# radar.net
KiCad netlist of a schematic drawn in EAGLE
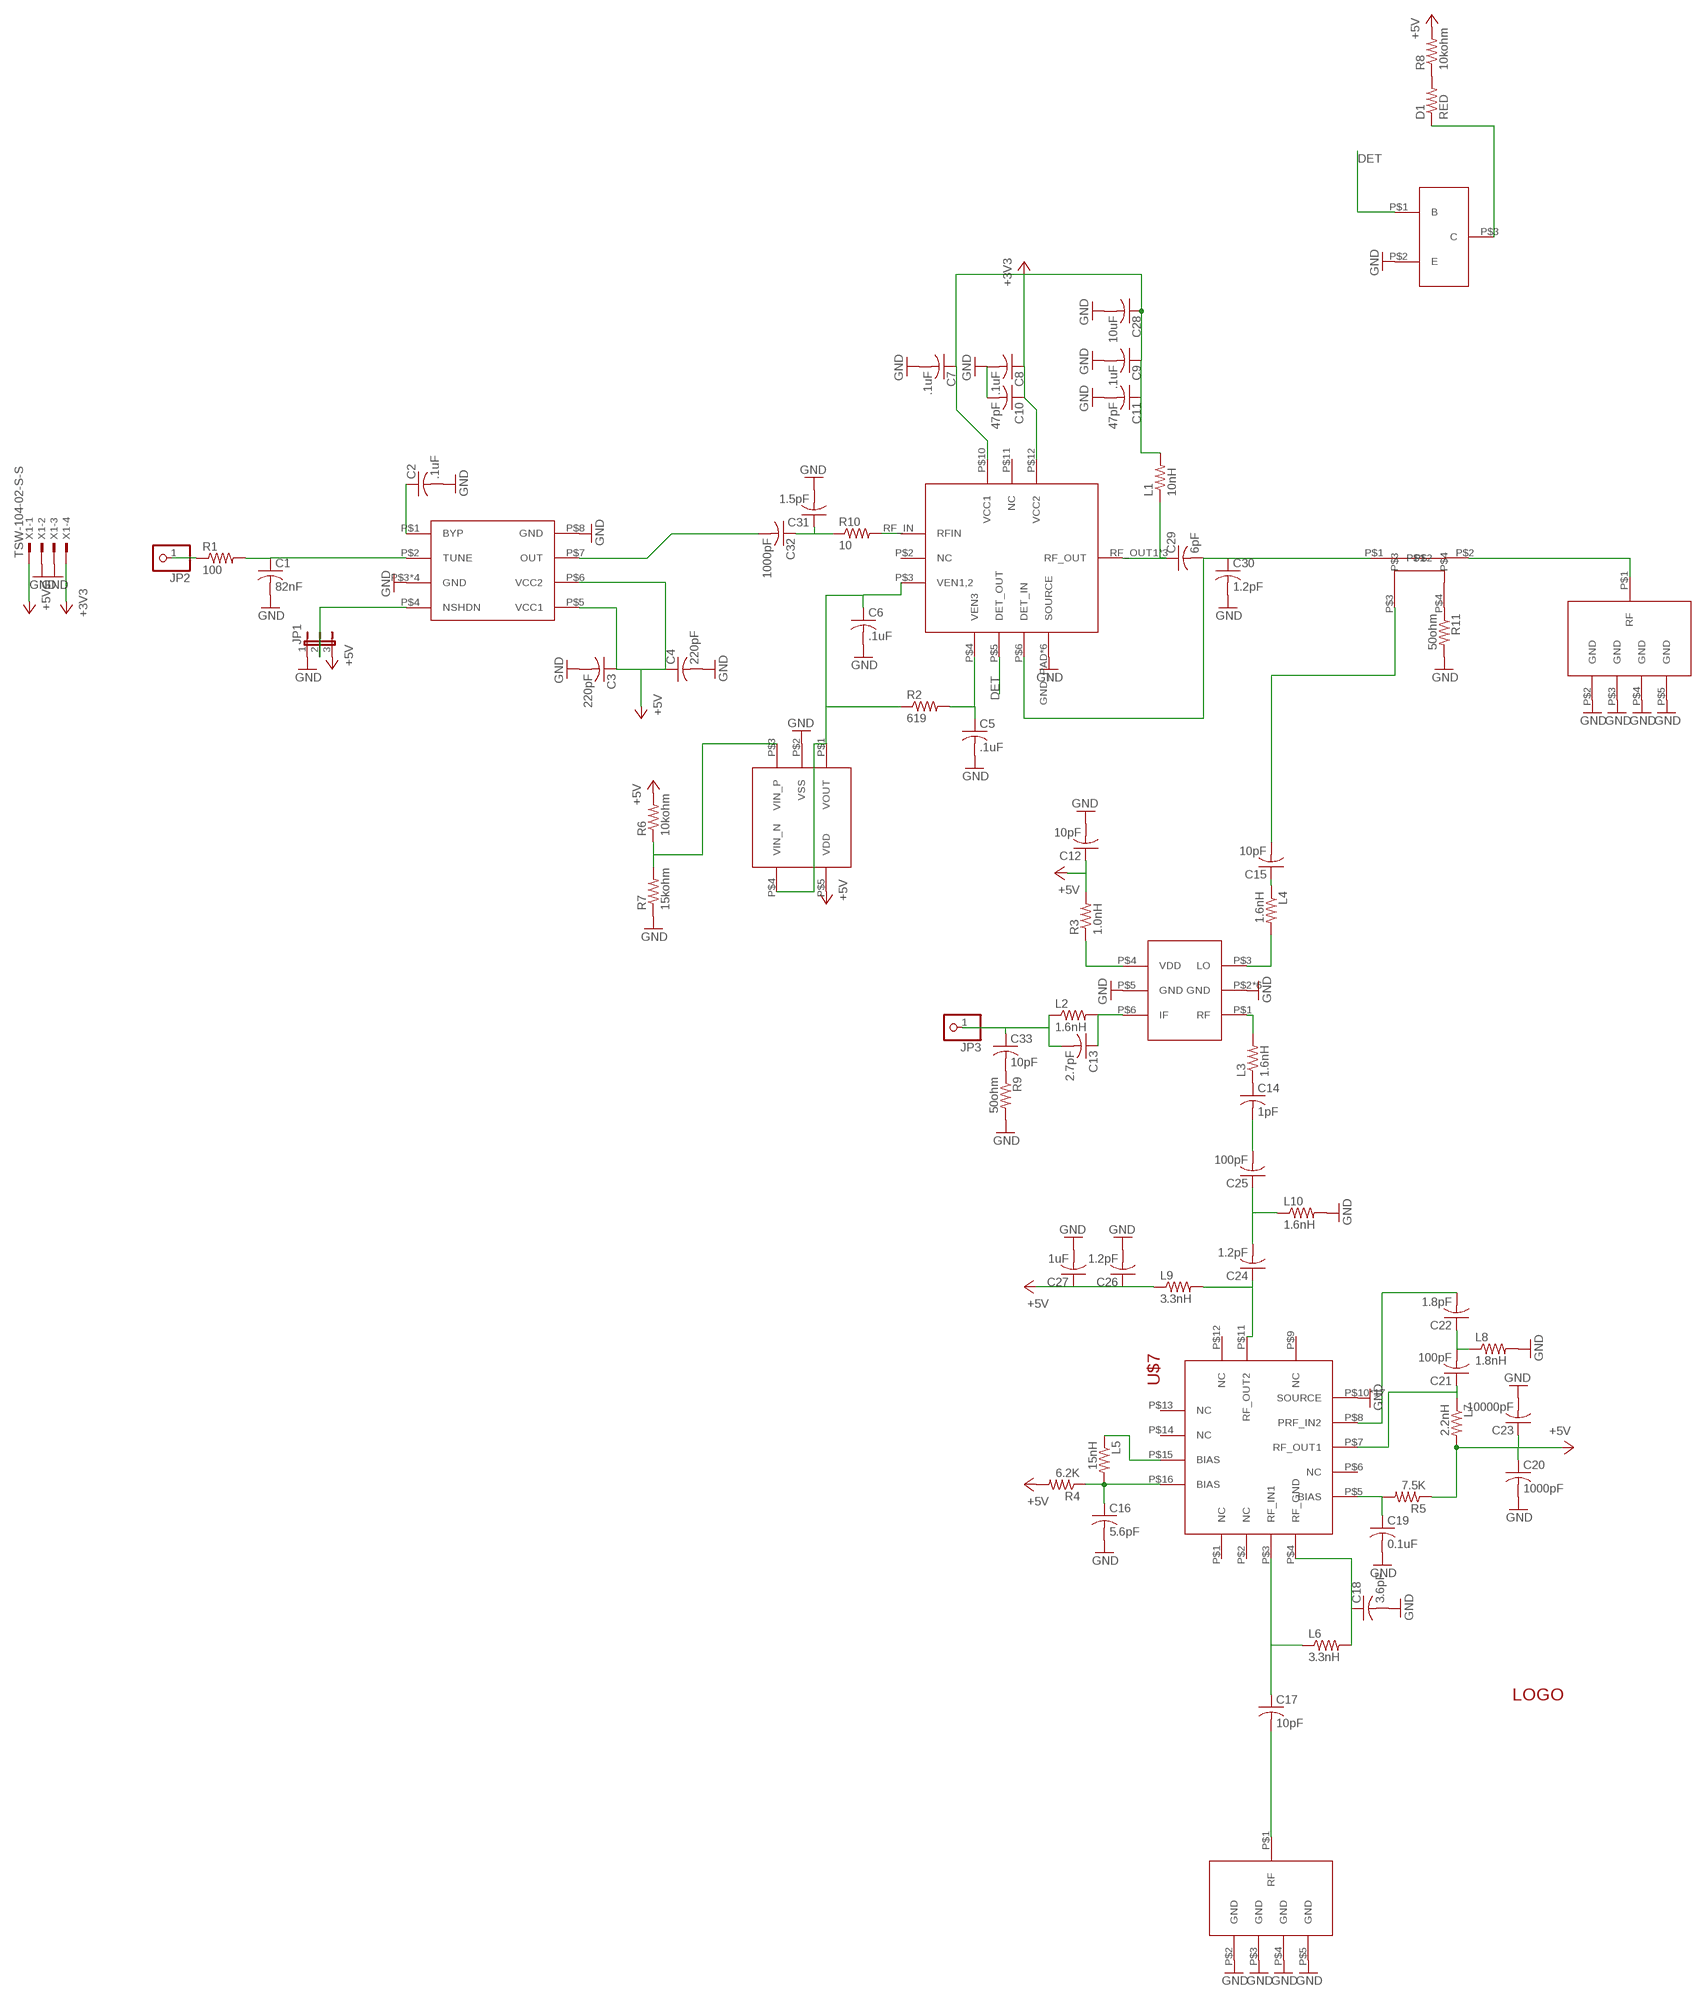
[diagram p0: schematic, sheet 1]

(export (version "E")
  (design (tool "Eeschema 10.0.6"))
  (components
    (comp (ref "C1")
      (value "82nF")
      (footprint "eagle-import:C3216")
      (fields (field (name "MANUFACTURER") "Vishay") (field (name "PART#") "VJ1206Y823MXBTW1BC"))
      (libsource (lib "eagle-import") (part "resistor_C-USC3216"))
    )
    (comp (ref "C2")
      (value ".1uF")
      (footprint "eagle-import:C0805")
      (fields (field (name "MANUFACTURER") "Vishay") (field (name "PART#") "VJ0805Y104MXXAC"))
      (libsource (lib "eagle-import") (part "C-USC0805"))
    )
    (comp (ref "C3")
      (value "220pF")
      (footprint "eagle-import:C0805")
      (fields (field (name "MANUFACTURER") "Vishay") (field (name "PART#") "VJ0805A221JXAPW1BC"))
      (libsource (lib "eagle-import") (part "C-USC0805"))
    )
    (comp (ref "C4")
      (value "220pF")
      (footprint "eagle-import:C0805")
      (fields (field (name "MANUFACTURER") "Vishay") (field (name "PART#") "VJ0805A221JXAPW1BC"))
      (libsource (lib "eagle-import") (part "C-USC0805"))
    )
    (comp (ref "C5")
      (value ".1uF")
      (footprint "eagle-import:C0805")
      (fields (field (name "MANUFACTURER") "Vishay") (field (name "PART#") "VJ0805Y104MXXAC"))
      (libsource (lib "eagle-import") (part "C-USC0805"))
    )
    (comp (ref "C6")
      (value ".1uF")
      (footprint "eagle-import:C0805")
      (fields (field (name "MANUFACTURER") "Vishay") (field (name "PART#") "VJ0805Y104MXXAC"))
      (libsource (lib "eagle-import") (part "C-USC0805"))
    )
    (comp (ref "C7")
      (value ".1uF")
      (footprint "eagle-import:C0805")
      (fields (field (name "MANUFACTURER") "Vishay") (field (name "PART#") "VJ0805Y104MXXAC"))
      (libsource (lib "eagle-import") (part "C-USC0805"))
    )
    (comp (ref "C8")
      (value ".1uF")
      (footprint "eagle-import:C0805")
      (fields (field (name "MANUFACTURER") "Vishay") (field (name "PART#") "VJ0805Y104MXXAC"))
      (libsource (lib "eagle-import") (part "C-USC0805"))
    )
    (comp (ref "C9")
      (value ".1uF")
      (footprint "eagle-import:C0805")
      (fields (field (name "MANUFACTURER") "Vishay") (field (name "PART#") "VJ0805Y104MXXAC"))
      (libsource (lib "eagle-import") (part "C-USC0805"))
    )
    (comp (ref "C10")
      (value "47pF")
      (footprint "eagle-import:C0805")
      (fields (field (name "MANUFACTURER") "Vishay") (field (name "PART#") "VJ0805A470GXACW1BC"))
      (libsource (lib "eagle-import") (part "C-USC0805"))
    )
    (comp (ref "C11")
      (value "47pF")
      (footprint "eagle-import:C0805")
      (fields (field (name "MANUFACTURER") "Vishay") (field (name "PART#") "VJ0805A470GXACW1BC"))
      (libsource (lib "eagle-import") (part "C-USC0805"))
    )
    (comp (ref "C12")
      (value "10pF")
      (footprint "eagle-import:C0805")
      (fields (field (name "MANUFACTURER") "Vishay") (field (name "PART#") "VJ0603A100JXACW1BC"))
      (libsource (lib "eagle-import") (part "C-USC0805"))
    )
    (comp (ref "C13")
      (value "2.7pF")
      (footprint "eagle-import:C0603")
      (fields (field (name "MANUFACTURER") "Vishay") (field (name "PART#") "VJ0603A2R7CXACW1BC"))
      (libsource (lib "eagle-import") (part "C-USC0603"))
    )
    (comp (ref "C14")
      (value "1pF")
      (footprint "eagle-import:C0603")
      (fields (field (name "MANUFACTURER") "Vishay") (field (name "PART#") "VJ0603A1R0CXACW1BC"))
      (libsource (lib "eagle-import") (part "C-USC0603"))
    )
    (comp (ref "C15")
      (value "10pF")
      (footprint "eagle-import:C0603")
      (fields (field (name "MANUFACTURER") "Vishay") (field (name "PART#") "VJ0603A2R7CXACW1BC"))
      (libsource (lib "eagle-import") (part "C-USC0603"))
    )
    (comp (ref "C16")
      (value "5.6pF")
      (footprint "eagle-import:C0603")
      (fields (field (name "MANUFACTURER") "Vishay") (field (name "PART#") "VJ0603A5R6CXACW1BC"))
      (libsource (lib "eagle-import") (part "C-USC0603"))
    )
    (comp (ref "C17")
      (value "10pF")
      (footprint "eagle-import:C0603")
      (fields (field (name "MANUFACTURER") "Vishay") (field (name "PART#") "VJ0603A100JXACW1BC"))
      (libsource (lib "eagle-import") (part "C-USC0603"))
    )
    (comp (ref "C18")
      (value "3.6pF")
      (footprint "eagle-import:C0603")
      (fields (field (name "MANUFACTURER") "Vishay") (field (name "PART#") "VJ0603A3R9CXACW1BC"))
      (libsource (lib "eagle-import") (part "C-USC0603"))
    )
    (comp (ref "C19")
      (value "0.1uF")
      (footprint "eagle-import:C0603")
      (fields (field (name "MANUFACTURER") "Vishay") (field (name "PART#") "VJ0603A3R9CXACW1BC"))
      (libsource (lib "eagle-import") (part "C-USC0603"))
    )
    (comp (ref "C20")
      (value "1000pF")
      (footprint "eagle-import:C0603")
      (fields (field (name "MANUFACTURER") "Vishay") (field (name "PART#") "VJ0603A3R9CXACW1BC"))
      (libsource (lib "eagle-import") (part "C-USC0603"))
    )
    (comp (ref "C21")
      (value "100pF")
      (footprint "eagle-import:C0603")
      (fields (field (name "MANUFACTURER") "Vishay") (field (name "PART#") "VJ0603A3R9CXACW1BC"))
      (libsource (lib "eagle-import") (part "C-USC0603"))
    )
    (comp (ref "C22")
      (value "1.8pF")
      (footprint "eagle-import:C0603")
      (fields (field (name "MANUFACTURER") "Vishay") (field (name "PART#") "VJ0603A3R9CXACW1BC"))
      (libsource (lib "eagle-import") (part "C-USC0603"))
    )
    (comp (ref "C23")
      (value "10000pF")
      (footprint "eagle-import:C0603")
      (fields (field (name "MANUFACTURER") "Vishay") (field (name "PART#") "VJ0603A3R9CXACW1BC"))
      (libsource (lib "eagle-import") (part "C-USC0603"))
    )
    (comp (ref "C24")
      (value "1.2pF")
      (footprint "eagle-import:C0603")
      (fields (field (name "MANUFACTURER") "Vishay") (field (name "PART#") "VJ0603A3R9CXACW1BC"))
      (libsource (lib "eagle-import") (part "C-USC0603"))
    )
    (comp (ref "C25")
      (value "100pF")
      (footprint "eagle-import:C0603")
      (fields (field (name "MANUFACTURER") "Vishay") (field (name "PART#") "VJ0603A3R9CXACW1BC"))
      (libsource (lib "eagle-import") (part "C-USC0603"))
    )
    (comp (ref "C26")
      (value "1.2pF")
      (footprint "eagle-import:C0603")
      (fields (field (name "MANUFACTURER") "Vishay") (field (name "PART#") "VJ0603A3R9CXACW1BC"))
      (libsource (lib "eagle-import") (part "C-USC0603"))
    )
    (comp (ref "C27")
      (value "1uF")
      (footprint "eagle-import:C0603")
      (fields (field (name "MANUFACTURER") "Vishay") (field (name "PART#") "VJ0603A3R9CXACW1BC"))
      (libsource (lib "eagle-import") (part "C-USC0603"))
    )
    (comp (ref "C28")
      (value "10uF")
      (footprint "eagle-import:C1206")
      (fields (field (name "MANUFACTURER") "Vishay") (field (name "PART#") "VJ1206V106ZXQTW1BC"))
      (libsource (lib "eagle-import") (part "C-USC1206"))
    )
    (comp (ref "C29")
      (value "6pF")
      (footprint "eagle-import:C0603")
      (fields (field (name "MANUFACTURER") "Vishay") (field (name "PART#") "VJ0805Y104MXXAC"))
      (libsource (lib "eagle-import") (part "C-USC0603"))
    )
    (comp (ref "C30")
      (value "1.2pF")
      (footprint "eagle-import:C0603")
      (fields (field (name "MANUFACTURER") "Vishay") (field (name "PART#") "VJ0805Y104MXXAC"))
      (libsource (lib "eagle-import") (part "C-USC0603"))
    )
    (comp (ref "C31")
      (value "1.5pF")
      (footprint "eagle-import:C0603K")
      (fields (field (name "MANUFACTURER") "Vishay") (field (name "PART#") "VJ0805Y104MXXAC"))
      (libsource (lib "eagle-import") (part "C-USC0603K"))
    )
    (comp (ref "C32")
      (value "1000pF")
      (footprint "eagle-import:C0603K")
      (fields (field (name "MANUFACTURER") "Vishay") (field (name "PART#") "VJ0805Y104MXXAC"))
      (libsource (lib "eagle-import") (part "C-USC0603K"))
    )
    (comp (ref "C33")
      (value "10pF")
      (footprint "eagle-import:C0805")
      (fields (field (name "MANUFACTURER") "Vishay") (field (name "PART#") "VJ0805A100GXAPW1BC"))
      (libsource (lib "eagle-import") (part "C-USC0805"))
    )
    (comp (ref "D1")
      (value "RED")
      (footprint "eagle-import:R1206")
      (fields (field (name "MANUFACTURER") "Vishay") (field (name "PART#") "VJ1206Y823MXBTW1BC"))
      (libsource (lib "eagle-import") (part "R-US_R1206"))
    )
    (comp (ref "JP1")
      (value "JP2E")
      (footprint "eagle-import:JP2")
      (libsource (lib "eagle-import") (part "JP2E"))
    )
    (comp (ref "JP2")
      (value "PINHD-1X1")
      (footprint "eagle-import:1X01")
      (libsource (lib "eagle-import") (part "PINHD-1X1"))
    )
    (comp (ref "JP3")
      (value "PINHD-1X1")
      (footprint "eagle-import:1X01")
      (libsource (lib "eagle-import") (part "PINHD-1X1"))
    )
    (comp (ref "L1")
      (value "10nH")
      (footprint "eagle-import:R0603")
      (fields (field (name "MANUFACTURER") "Taiyo Yuden") (field (name "PART#") "HK060310NJ-T"))
      (libsource (lib "eagle-import") (part "R-US_R0603"))
    )
    (comp (ref "L2")
      (value "1.6nH")
      (footprint "eagle-import:R0603")
      (fields (field (name "MANUFACTURER") "TE Connectivity") (field (name "PART#") "HK060310NJ-T"))
      (libsource (lib "eagle-import") (part "R-US_R0603"))
    )
    (comp (ref "L3")
      (value "1.6nH")
      (footprint "eagle-import:R0603")
      (fields (field (name "MANUFACTURER") "TE Connectivity") (field (name "PART#") "HK060310NJ-T"))
      (libsource (lib "eagle-import") (part "R-US_R0603"))
    )
    (comp (ref "L4")
      (value "1.6nH")
      (footprint "eagle-import:R0603")
      (fields (field (name "MANUFACTURER") "TE Connectivity") (field (name "PART#") "HK060310NJ-T"))
      (libsource (lib "eagle-import") (part "R-US_R0603"))
    )
    (comp (ref "L5")
      (value "15nH")
      (footprint "eagle-import:R0603")
      (fields (field (name "MANUFACTURER") "Taiyo Yuden") (field (name "PART#") "HK160815NJ-T"))
      (libsource (lib "eagle-import") (part "R-US_R0603"))
    )
    (comp (ref "L6")
      (value "3.3nH")
      (footprint "eagle-import:R0603")
      (fields (field (name "MANUFACTURER") "Taiyo Yuden") (field (name "PART#") "HK16083N3S-T"))
      (libsource (lib "eagle-import") (part "R-US_R0603"))
    )
    (comp (ref "L7")
      (value "2.2nH")
      (footprint "eagle-import:R0603")
      (fields (field (name "MANUFACTURER") "Taiyo Yuden") (field (name "PART#") "HK16083N3S-T"))
      (libsource (lib "eagle-import") (part "R-US_R0603"))
    )
    (comp (ref "L8")
      (value "1.8nH")
      (footprint "eagle-import:R0603")
      (fields (field (name "MANUFACTURER") "Taiyo Yuden") (field (name "PART#") "HK16083N3S-T"))
      (libsource (lib "eagle-import") (part "R-US_R0603"))
    )
    (comp (ref "L9")
      (value "3.3nH")
      (footprint "eagle-import:R0603")
      (fields (field (name "MANUFACTURER") "Taiyo Yuden") (field (name "PART#") "HK16083N3S-T"))
      (libsource (lib "eagle-import") (part "R-US_R0603"))
    )
    (comp (ref "L10")
      (value "1.6nH")
      (footprint "eagle-import:R0603")
      (fields (field (name "MANUFACTURER") "TE Connectivity") (field (name "PART#") "HK060310NJ-T"))
      (libsource (lib "eagle-import") (part "R-US_R0603"))
    )
    (comp (ref "R1")
      (value "100")
      (footprint "eagle-import:R1206")
      (fields (field (name "MANUFACTURER") "Vishay") (field (name "PART#") "VJ1206Y823MXBTW1BC"))
      (libsource (lib "eagle-import") (part "R-US_R1206"))
    )
    (comp (ref "R2")
      (value "619")
      (footprint "eagle-import:R0805")
      (fields (field (name "MANUFACTURER") "Vishay") (field (name "PART#") "CRCW0805619RFKEA"))
      (libsource (lib "eagle-import") (part "R-US_R0805"))
    )
    (comp (ref "R3")
      (value "1.0nH")
      (footprint "eagle-import:R0402")
      (fields (field (name "MANUFACTURER") "Vishay") (field (name "PART#") "ILC0402ER1N0S"))
      (libsource (lib "eagle-import") (part "R-US_R0402"))
    )
    (comp (ref "R4")
      (value "6.2K")
      (footprint "eagle-import:R0603")
      (fields (field (name "MANUFACTURER") "Vishay") (field (name "PART#") "CRCW06036K20FKEA"))
      (libsource (lib "eagle-import") (part "R-US_R0603"))
    )
    (comp (ref "R5")
      (value "7.5K")
      (footprint "eagle-import:R0603")
      (fields (field (name "MANUFACTURER") "Vishay") (field (name "PART#") "CRCW06036K20FKEA"))
      (libsource (lib "eagle-import") (part "R-US_R0603"))
    )
    (comp (ref "R6")
      (value "10kohm")
      (footprint "eagle-import:R1206")
      (fields (field (name "MANUFACTURER") "Vishay") (field (name "PART#") "VJ1206Y823MXBTW1BC"))
      (libsource (lib "eagle-import") (part "R-US_R1206"))
    )
    (comp (ref "R7")
      (value "15kohm")
      (footprint "eagle-import:R1206")
      (fields (field (name "MANUFACTURER") "Vishay") (field (name "PART#") "VJ1206Y823MXBTW1BC"))
      (libsource (lib "eagle-import") (part "R-US_R1206"))
    )
    (comp (ref "R8")
      (value "10kohm")
      (footprint "eagle-import:R1206")
      (fields (field (name "MANUFACTURER") "Vishay") (field (name "PART#") "VJ1206Y823MXBTW1BC"))
      (libsource (lib "eagle-import") (part "R-US_R1206"))
    )
    (comp (ref "R9")
      (value "50ohm")
      (footprint "eagle-import:R0805")
      (fields (field (name "MANUFACTURER") "Vishay") (field (name "PART#") "CRCW080550R0FKTA"))
      (libsource (lib "eagle-import") (part "R-US_R0805"))
    )
    (comp (ref "R10")
      (value "10")
      (footprint "eagle-import:R0603")
      (fields (field (name "MANUFACTURER") "Vishay") (field (name "PART#") "CRCW0805619RFKEA"))
      (libsource (lib "eagle-import") (part "R-US_R0603"))
    )
    (comp (ref "R11")
      (value "50ohm")
      (footprint "eagle-import:R0805")
      (fields (field (name "MANUFACTURER") "Vishay") (field (name "PART#") "CRCW080550R0FKTA"))
      (libsource (lib "eagle-import") (part "R-US_R0805"))
    )
    (comp (ref "U$1")
      (value "COUPLER")
      (footprint "eagle-import:COUPLER")
      (libsource (lib "eagle-import") (part "COUPLER"))
    )
    (comp (ref "U$2")
      (value "MAAPSS0075")
      (footprint "eagle-import:MAAPSS075")
      (libsource (lib "eagle-import") (part "MAAPSS0075"))
    )
    (comp (ref "U$3")
      (value "CMY210")
      (footprint "eagle-import:CMY210")
      (libsource (lib "eagle-import") (part "CMY210"))
    )
    (comp (ref "U$4")
      (value "SMA")
      (footprint "eagle-import:SMA")
      (libsource (lib "eagle-import") (part "SMA"))
    )
    (comp (ref "U$6")
      (value "SMA")
      (footprint "eagle-import:SMA")
      (libsource (lib "eagle-import") (part "SMA"))
    )
    (comp (ref "U$7")
      (value "SKY67107")
      (footprint "eagle-import:SKY67107")
      (libsource (lib "eagle-import") (part "SKY67107"))
    )
    (comp (ref "U$9")
      (value "MCP6001")
      (footprint "eagle-import:SOT-23-5")
      (libsource (lib "eagle-import") (part "MCP6001"))
    )
    (comp (ref "U$10")
      (value "MMBT3904")
      (footprint "eagle-import:SOT23-3")
      (libsource (lib "eagle-import") (part "MMBT3904"))
    )
    (comp (ref "U$11")
      (value "LOGO")
      (footprint "eagle-import:LOGO")
      (libsource (lib "eagle-import") (part "LOGO"))
    )
    (comp (ref "U1")
      (value "MAX2750")
      (footprint "eagle-import:MAX2750")
      (libsource (lib "eagle-import") (part "MAX2750"))
    )
    (comp (ref "X1")
      (value "TSW-104-02-S-S")
      (footprint "eagle-import:TSW-104-02-S-S")
      (libsource (lib "eagle-import") (part "TSW-104-02-S-S"))
    )
  )
  (nets
    (net (code "1") (name "+3V3") (class "Default")
      (node (ref "C10") (pin "1") (pinfunction "1_1") (pintype "passive"))
      (node (ref "C11") (pin "1") (pinfunction "1_1") (pintype "passive"))
      (node (ref "C28") (pin "1") (pinfunction "1_1") (pintype "passive"))
      (node (ref "C7") (pin "1") (pinfunction "1_1") (pintype "passive"))
      (node (ref "C8") (pin "1") (pinfunction "1_1") (pintype "passive"))
      (node (ref "C9") (pin "1") (pinfunction "1_1") (pintype "passive"))
      (node (ref "L1") (pin "2") (pinfunction "2_2") (pintype "passive"))
      (node (ref "U$2") (pin "P$10") (pinfunction "VCC1_P$10") (pintype "power_in"))
      (node (ref "U$2") (pin "P$12") (pinfunction "VCC2_P$12") (pintype "power_in"))
      (node (ref "X1") (pin "4") (pinfunction "1_4") (pintype "passive"))
    )
    (net (code "2") (name "+5V") (class "Default")
      (node (ref "C12") (pin "1") (pinfunction "1_1") (pintype "passive"))
      (node (ref "C20") (pin "1") (pinfunction "1_1") (pintype "passive"))
      (node (ref "C23") (pin "1") (pinfunction "1_1") (pintype "passive"))
      (node (ref "C26") (pin "1") (pinfunction "1_1") (pintype "passive"))
      (node (ref "C27") (pin "1") (pinfunction "1_1") (pintype "passive"))
      (node (ref "C3") (pin "1") (pinfunction "1_1") (pintype "passive"))
      (node (ref "C4") (pin "1") (pinfunction "1_1") (pintype "passive"))
      (node (ref "JP1") (pin "3") (pinfunction "3_3") (pintype "passive"))
      (node (ref "L7") (pin "2") (pinfunction "2_2") (pintype "passive"))
      (node (ref "L9") (pin "1") (pinfunction "1_1") (pintype "passive"))
      (node (ref "R3") (pin "2") (pinfunction "2_2") (pintype "passive"))
      (node (ref "R4") (pin "2") (pinfunction "2_2") (pintype "passive"))
      (node (ref "R5") (pin "1") (pinfunction "1_1") (pintype "passive"))
      (node (ref "R6") (pin "2") (pinfunction "2_2") (pintype "passive"))
      (node (ref "R8") (pin "2") (pinfunction "2_2") (pintype "passive"))
      (node (ref "U$9") (pin "P$5") (pinfunction "VDD_P$5") (pintype "bidirectional"))
      (node (ref "U1") (pin "P$5") (pinfunction "VCC1_P$5") (pintype "power_in"))
      (node (ref "U1") (pin "P$6") (pinfunction "VCC2_P$6") (pintype "power_in"))
      (node (ref "X1") (pin "1") (pinfunction "1_1") (pintype "passive"))
    )
    (net (code "3") (name "/DET") (class "Default")
      (node (ref "U$10") (pin "P$1") (pinfunction "B_P$1") (pintype "bidirectional"))
      (node (ref "U$2") (pin "P$5") (pinfunction "DET_OUT_P$5") (pintype "output"))
    )
    (net (code "4") (name "GND") (class "Default")
      (node (ref "C1") (pin "2") (pinfunction "2_2") (pintype "passive"))
      (node (ref "C10") (pin "2") (pinfunction "2_2") (pintype "passive"))
      (node (ref "C11") (pin "2") (pinfunction "2_2") (pintype "passive"))
      (node (ref "C12") (pin "2") (pinfunction "2_2") (pintype "passive"))
      (node (ref "C16") (pin "2") (pinfunction "2_2") (pintype "passive"))
      (node (ref "C18") (pin "2") (pinfunction "2_2") (pintype "passive"))
      (node (ref "C19") (pin "2") (pinfunction "2_2") (pintype "passive"))
      (node (ref "C2") (pin "2") (pinfunction "2_2") (pintype "passive"))
      (node (ref "C20") (pin "2") (pinfunction "2_2") (pintype "passive"))
      (node (ref "C23") (pin "2") (pinfunction "2_2") (pintype "passive"))
      (node (ref "C26") (pin "2") (pinfunction "2_2") (pintype "passive"))
      (node (ref "C27") (pin "2") (pinfunction "2_2") (pintype "passive"))
      (node (ref "C28") (pin "2") (pinfunction "2_2") (pintype "passive"))
      (node (ref "C3") (pin "2") (pinfunction "2_2") (pintype "passive"))
      (node (ref "C30") (pin "2") (pinfunction "2_2") (pintype "passive"))
      (node (ref "C31") (pin "2") (pinfunction "2_2") (pintype "passive"))
      (node (ref "C4") (pin "2") (pinfunction "2_2") (pintype "passive"))
      (node (ref "C5") (pin "2") (pinfunction "2_2") (pintype "passive"))
      (node (ref "C6") (pin "2") (pinfunction "2_2") (pintype "passive"))
      (node (ref "C7") (pin "2") (pinfunction "2_2") (pintype "passive"))
      (node (ref "C8") (pin "2") (pinfunction "2_2") (pintype "passive"))
      (node (ref "C9") (pin "2") (pinfunction "2_2") (pintype "passive"))
      (node (ref "JP1") (pin "1") (pinfunction "1_1") (pintype "passive"))
      (node (ref "L10") (pin "2") (pinfunction "2_2") (pintype "passive"))
      (node (ref "L8") (pin "2") (pinfunction "2_2") (pintype "passive"))
      (node (ref "R11") (pin "2") (pinfunction "2_2") (pintype "passive"))
      (node (ref "R7") (pin "1") (pinfunction "1_1") (pintype "passive"))
      (node (ref "R9") (pin "2") (pinfunction "2_2") (pintype "passive"))
      (node (ref "U$10") (pin "P$2") (pinfunction "E_P$2") (pintype "bidirectional"))
      (node (ref "U$2") (pin "GND_PAD") (pinfunction "SOURCE_GND_PAD") (pintype "bidirectional"))
      (node (ref "U$2") (pin "P$1") (pinfunction "SOURCE_P$1") (pintype "bidirectional"))
      (node (ref "U$2") (pin "P$14") (pinfunction "SOURCE_P$14") (pintype "bidirectional"))
      (node (ref "U$2") (pin "P$7") (pinfunction "SOURCE_P$7") (pintype "bidirectional"))
      (node (ref "U$2") (pin "P$8") (pinfunction "SOURCE_P$8") (pintype "bidirectional"))
      (node (ref "U$2") (pin "P$9") (pinfunction "SOURCE_P$9") (pintype "bidirectional"))
      (node (ref "U$3") (pin "P$10") (pinfunction "GND_P$10") (pintype "bidirectional"))
      (node (ref "U$3") (pin "P$11") (pinfunction "GND_P$11") (pintype "bidirectional"))
      (node (ref "U$3") (pin "P$2") (pinfunction "GND_P$2") (pintype "bidirectional"))
      (node (ref "U$3") (pin "P$5") (pinfunction "GND_P$5") (pintype "bidirectional"))
      (node (ref "U$3") (pin "P$7") (pinfunction "GND_P$7") (pintype "bidirectional"))
      (node (ref "U$3") (pin "P$8") (pinfunction "GND_P$8") (pintype "bidirectional"))
      (node (ref "U$3") (pin "P$9") (pinfunction "GND_P$9") (pintype "bidirectional"))
      (node (ref "U$4") (pin "P$2") (pinfunction "GND_P$2") (pintype "power_in"))
      (node (ref "U$4") (pin "P$3") (pinfunction "GND_P$3") (pintype "power_in"))
      (node (ref "U$4") (pin "P$4") (pinfunction "GND_P$4") (pintype "power_in"))
      (node (ref "U$4") (pin "P$5") (pinfunction "GND_P$5") (pintype "power_in"))
      (node (ref "U$6") (pin "P$2") (pinfunction "GND_P$2") (pintype "power_in"))
      (node (ref "U$6") (pin "P$3") (pinfunction "GND_P$3") (pintype "power_in"))
      (node (ref "U$6") (pin "P$4") (pinfunction "GND_P$4") (pintype "power_in"))
      (node (ref "U$6") (pin "P$5") (pinfunction "GND_P$5") (pintype "power_in"))
      (node (ref "U$7") (pin "P$10") (pinfunction "SOURCE_P$10") (pintype "bidirectional"))
      (node (ref "U$7") (pin "P$17") (pinfunction "SOURCE_P$17") (pintype "bidirectional"))
      (node (ref "U$7") (pin "P$18") (pinfunction "SOURCE_P$18") (pintype "bidirectional"))
      (node (ref "U$7") (pin "P$19") (pinfunction "SOURCE_P$19") (pintype "bidirectional"))
      (node (ref "U$7") (pin "P$20") (pinfunction "SOURCE_P$20") (pintype "bidirectional"))
      (node (ref "U$7") (pin "P$21") (pinfunction "SOURCE_P$21") (pintype "bidirectional"))
      (node (ref "U$7") (pin "P$22") (pinfunction "SOURCE_P$22") (pintype "bidirectional"))
      (node (ref "U$7") (pin "P$23") (pinfunction "SOURCE_P$23") (pintype "bidirectional"))
      (node (ref "U$7") (pin "P$24") (pinfunction "SOURCE_P$24") (pintype "bidirectional"))
      (node (ref "U$7") (pin "P$25") (pinfunction "SOURCE_P$25") (pintype "bidirectional"))
      (node (ref "U$7") (pin "P$26") (pinfunction "SOURCE_P$26") (pintype "bidirectional"))
      (node (ref "U$7") (pin "P$27") (pinfunction "SOURCE_P$27") (pintype "bidirectional"))
      (node (ref "U$7") (pin "P$28") (pinfunction "SOURCE_P$28") (pintype "bidirectional"))
      (node (ref "U$7") (pin "P$29") (pinfunction "SOURCE_P$29") (pintype "bidirectional"))
      (node (ref "U$7") (pin "P$30") (pinfunction "SOURCE_P$30") (pintype "bidirectional"))
      (node (ref "U$7") (pin "P$31") (pinfunction "SOURCE_P$31") (pintype "bidirectional"))
      (node (ref "U$7") (pin "P$32") (pinfunction "SOURCE_P$32") (pintype "bidirectional"))
      (node (ref "U$9") (pin "P$2") (pinfunction "VSS_P$2") (pintype "bidirectional"))
      (node (ref "U1") (pin "P$11") (pinfunction "GND_P$11") (pintype "power_in"))
      (node (ref "U1") (pin "P$13") (pinfunction "GND_P$13") (pintype "power_in"))
      (node (ref "U1") (pin "P$3") (pinfunction "GND_P$3") (pintype "power_in"))
      (node (ref "U1") (pin "P$8") (pinfunction "GND_P$8") (pintype "power_in"))
      (node (ref "U1") (pin "P$9") (pinfunction "GND_P$9") (pintype "power_in"))
      (node (ref "X1") (pin "2") (pinfunction "1_2") (pintype "passive"))
      (node (ref "X1") (pin "3") (pinfunction "1_3") (pintype "passive"))
    )
    (net (code "5") (name "Net-(C13-Pad2)") (class "Default")
      (node (ref "C13") (pin "2") (pinfunction "2_2") (pintype "passive"))
      (node (ref "C33") (pin "1") (pinfunction "1_1") (pintype "passive"))
      (node (ref "JP3") (pin "1") (pinfunction "1_1") (pintype "passive"))
      (node (ref "L2") (pin "1") (pinfunction "1_1") (pintype "passive"))
    )
    (net (code "6") (name "Net-(C14-Pad1)") (class "Default")
      (node (ref "C14") (pin "1") (pinfunction "1_1") (pintype "passive"))
      (node (ref "L3") (pin "1") (pinfunction "1_1") (pintype "passive"))
    )
    (net (code "7") (name "Net-(C14-Pad2)") (class "Default")
      (node (ref "C14") (pin "2") (pinfunction "2_2") (pintype "passive"))
      (node (ref "C25") (pin "2") (pinfunction "2_2") (pintype "passive"))
    )
    (net (code "8") (name "Net-(C15-Pad1)") (class "Default")
      (node (ref "C15") (pin "1") (pinfunction "1_1") (pintype "passive"))
      (node (ref "L4") (pin "1") (pinfunction "1_1") (pintype "passive"))
    )
    (net (code "9") (name "Net-(C15-Pad2)") (class "Default")
      (node (ref "C15") (pin "2") (pinfunction "2_2") (pintype "passive"))
      (node (ref "U$1") (pin "P$3") (pinfunction "P$3_P$3") (pintype "bidirectional"))
    )
    (net (code "10") (name "Net-(C16-Pad1)") (class "Default")
      (node (ref "C16") (pin "1") (pinfunction "1_1") (pintype "passive"))
      (node (ref "L5") (pin "2") (pinfunction "2_2") (pintype "passive"))
      (node (ref "R4") (pin "1") (pinfunction "1_1") (pintype "passive"))
      (node (ref "U$7") (pin "P$16") (pinfunction "BIAS_P$16") (pintype "bidirectional"))
    )
    (net (code "11") (name "Net-(C19-Pad1)") (class "Default")
      (node (ref "C19") (pin "1") (pinfunction "1_1") (pintype "passive"))
      (node (ref "R5") (pin "2") (pinfunction "2_2") (pintype "passive"))
      (node (ref "U$7") (pin "P$5") (pinfunction "BIAS_P$5") (pintype "bidirectional"))
    )
    (net (code "12") (name "Net-(C21-Pad2)") (class "Default")
      (node (ref "C21") (pin "2") (pinfunction "2_2") (pintype "passive"))
      (node (ref "C22") (pin "1") (pinfunction "1_1") (pintype "passive"))
      (node (ref "L8") (pin "1") (pinfunction "1_1") (pintype "passive"))
    )
    (net (code "13") (name "Net-(C24-Pad2)") (class "Default")
      (node (ref "C24") (pin "2") (pinfunction "2_2") (pintype "passive"))
      (node (ref "C25") (pin "1") (pinfunction "1_1") (pintype "passive"))
      (node (ref "L10") (pin "1") (pinfunction "1_1") (pintype "passive"))
    )
    (net (code "14") (name "Net-(C29-Pad1)") (class "Default")
      (node (ref "C29") (pin "1") (pinfunction "1_1") (pintype "passive"))
      (node (ref "L1") (pin "1") (pinfunction "1_1") (pintype "passive"))
      (node (ref "U$2") (pin "RF_OUT1") (pinfunction "RF_OUT_RF_OUT1") (pintype "open_collector"))
      (node (ref "U$2") (pin "RF_OUT2") (pinfunction "RF_OUT_RF_OUT2") (pintype "open_collector"))
      (node (ref "U$2") (pin "RF_OUT3") (pinfunction "RF_OUT_RF_OUT3") (pintype "open_collector"))
    )
    (net (code "15") (name "Net-(C31-Pad1)") (class "Default")
      (node (ref "C31") (pin "1") (pinfunction "1_1") (pintype "passive"))
      (node (ref "C32") (pin "1") (pinfunction "1_1") (pintype "passive"))
      (node (ref "R10") (pin "1") (pinfunction "1_1") (pintype "passive"))
    )
    (net (code "16") (name "Net-(C33-Pad2)") (class "Default")
      (node (ref "C33") (pin "2") (pinfunction "2_2") (pintype "passive"))
      (node (ref "R9") (pin "1") (pinfunction "1_1") (pintype "passive"))
    )
    (net (code "17") (name "Net-(D1-Pad2)") (class "Default")
      (node (ref "D1") (pin "2") (pinfunction "2_2") (pintype "passive"))
      (node (ref "R8") (pin "1") (pinfunction "1_1") (pintype "passive"))
    )
    (net (code "18") (name "Net-(JP2-Pad1)") (class "Default")
      (node (ref "JP2") (pin "1") (pinfunction "1_1") (pintype "passive"))
      (node (ref "R1") (pin "1") (pinfunction "1_1") (pintype "passive"))
    )
    (net (code "19") (name "Net-(L5-Pad1)") (class "Default")
      (node (ref "L5") (pin "1") (pinfunction "1_1") (pintype "passive"))
      (node (ref "U$7") (pin "P$15") (pinfunction "BIAS_P$15") (pintype "bidirectional"))
    )
    (net (code "20") (name "Net-(R11-Pad1)") (class "Default")
      (node (ref "R11") (pin "1") (pinfunction "1_1") (pintype "passive"))
      (node (ref "U$1") (pin "P$4") (pinfunction "P$4_P$4") (pintype "bidirectional"))
    )
    (net (code "21") (name "Net-(U$2-DET_IN)") (class "Default")
      (node (ref "C29") (pin "2") (pinfunction "2_2") (pintype "passive"))
      (node (ref "C30") (pin "1") (pinfunction "1_1") (pintype "passive"))
      (node (ref "U$1") (pin "P$1") (pinfunction "P$1_P$1") (pintype "bidirectional"))
      (node (ref "U$2") (pin "P$6") (pinfunction "DET_IN_P$6") (pintype "input"))
    )
    (net (code "22") (name "Net-(U$2-RFIN)") (class "Default")
      (node (ref "R10") (pin "2") (pinfunction "2_2") (pintype "passive"))
      (node (ref "U$2") (pin "RF_IN") (pinfunction "RFIN_RF_IN") (pintype "input"))
    )
    (net (code "23") (name "Net-(U$2-VEN1,2)") (class "Default")
      (node (ref "C6") (pin "1") (pinfunction "1_1") (pintype "passive"))
      (node (ref "R2") (pin "1") (pinfunction "1_1") (pintype "passive"))
      (node (ref "U$2") (pin "P$3") (pinfunction "VEN1,2_P$3") (pintype "input"))
      (node (ref "U$9") (pin "P$1") (pinfunction "VOUT_P$1") (pintype "bidirectional"))
      (node (ref "U$9") (pin "P$4") (pinfunction "VIN_N_P$4") (pintype "bidirectional"))
    )
    (net (code "24") (name "Net-(U$2-VEN3)") (class "Default")
      (node (ref "C5") (pin "1") (pinfunction "1_1") (pintype "passive"))
      (node (ref "R2") (pin "2") (pinfunction "2_2") (pintype "passive"))
      (node (ref "U$2") (pin "P$4") (pinfunction "VEN3_P$4") (pintype "input"))
    )
    (net (code "25") (name "Net-(U$3-IF)") (class "Default")
      (node (ref "C13") (pin "1") (pinfunction "1_1") (pintype "passive"))
      (node (ref "L2") (pin "2") (pinfunction "2_2") (pintype "passive"))
      (node (ref "U$3") (pin "P$6") (pinfunction "IF_P$6") (pintype "bidirectional"))
    )
    (net (code "26") (name "Net-(U$3-LO)") (class "Default")
      (node (ref "L4") (pin "2") (pinfunction "2_2") (pintype "passive"))
      (node (ref "U$3") (pin "P$3") (pinfunction "LO_P$3") (pintype "bidirectional"))
    )
    (net (code "27") (name "Net-(U$3-RF)") (class "Default")
      (node (ref "L3") (pin "2") (pinfunction "2_2") (pintype "passive"))
      (node (ref "U$3") (pin "P$1") (pinfunction "RF_P$1") (pintype "bidirectional"))
    )
    (net (code "28") (name "Net-(U$3-VDD)") (class "Default")
      (node (ref "R3") (pin "1") (pinfunction "1_1") (pintype "passive"))
      (node (ref "U$3") (pin "P$4") (pinfunction "VDD_P$4") (pintype "bidirectional"))
    )
    (net (code "29") (name "Net-(U$4-RF)") (class "Default")
      (node (ref "U$1") (pin "P$2") (pinfunction "P$2_P$2") (pintype "bidirectional"))
      (node (ref "U$4") (pin "P$1") (pinfunction "RF_P$1") (pintype "bidirectional"))
    )
    (net (code "30") (name "Net-(U$6-RF)") (class "Default")
      (node (ref "C17") (pin "2") (pinfunction "2_2") (pintype "passive"))
      (node (ref "U$6") (pin "P$1") (pinfunction "RF_P$1") (pintype "bidirectional"))
    )
    (net (code "31") (name "Net-(U$7-PRF_IN2)") (class "Default")
      (node (ref "C22") (pin "2") (pinfunction "2_2") (pintype "passive"))
      (node (ref "U$7") (pin "P$8") (pinfunction "PRF_IN2_P$8") (pintype "bidirectional"))
    )
    (net (code "32") (name "Net-(U$7-RF_GND)") (class "Default")
      (node (ref "C18") (pin "1") (pinfunction "1_1") (pintype "passive"))
      (node (ref "L6") (pin "2") (pinfunction "2_2") (pintype "passive"))
      (node (ref "U$7") (pin "P$4") (pinfunction "RF_GND_P$4") (pintype "bidirectional"))
    )
    (net (code "33") (name "Net-(U$7-RF_IN1)") (class "Default")
      (node (ref "C17") (pin "1") (pinfunction "1_1") (pintype "passive"))
      (node (ref "L6") (pin "1") (pinfunction "1_1") (pintype "passive"))
      (node (ref "U$7") (pin "P$3") (pinfunction "RF_IN1_P$3") (pintype "bidirectional"))
    )
    (net (code "34") (name "Net-(U$7-RF_OUT1)") (class "Default")
      (node (ref "C21") (pin "1") (pinfunction "1_1") (pintype "passive"))
      (node (ref "L7") (pin "1") (pinfunction "1_1") (pintype "passive"))
      (node (ref "U$7") (pin "P$7") (pinfunction "RF_OUT1_P$7") (pintype "bidirectional"))
    )
    (net (code "35") (name "Net-(U$7-RF_OUT2)") (class "Default")
      (node (ref "C24") (pin "1") (pinfunction "1_1") (pintype "passive"))
      (node (ref "L9") (pin "2") (pinfunction "2_2") (pintype "passive"))
      (node (ref "U$7") (pin "P$11") (pinfunction "RF_OUT2_P$11") (pintype "bidirectional"))
    )
    (net (code "36") (name "Net-(U$9-VIN_P)") (class "Default")
      (node (ref "R6") (pin "1") (pinfunction "1_1") (pintype "passive"))
      (node (ref "R7") (pin "2") (pinfunction "2_2") (pintype "passive"))
      (node (ref "U$9") (pin "P$3") (pinfunction "VIN_P_P$3") (pintype "bidirectional"))
    )
    (net (code "37") (name "Net-(U$10-C)") (class "Default")
      (node (ref "D1") (pin "1") (pinfunction "1_1") (pintype "passive"))
      (node (ref "U$10") (pin "P$3") (pinfunction "C_P$3") (pintype "bidirectional"))
    )
    (net (code "38") (name "Net-(U1-BYP)") (class "Default")
      (node (ref "C2") (pin "1") (pinfunction "1_1") (pintype "passive"))
      (node (ref "U1") (pin "P$1") (pinfunction "BYP_P$1") (pintype "passive"))
    )
    (net (code "39") (name "Net-(U1-NSHDN)") (class "Default")
      (node (ref "JP1") (pin "2") (pinfunction "2_2") (pintype "passive"))
      (node (ref "U1") (pin "P$4") (pinfunction "NSHDN_P$4") (pintype "input"))
    )
    (net (code "40") (name "Net-(U1-OUT)") (class "Default")
      (node (ref "C32") (pin "2") (pinfunction "2_2") (pintype "passive"))
      (node (ref "U1") (pin "P$7") (pinfunction "OUT_P$7") (pintype "output"))
    )
    (net (code "41") (name "Net-(U1-TUNE)") (class "Default")
      (node (ref "C1") (pin "1") (pinfunction "1_1") (pintype "passive"))
      (node (ref "R1") (pin "2") (pinfunction "2_2") (pintype "passive"))
      (node (ref "U1") (pin "P$2") (pinfunction "TUNE_P$2") (pintype "input"))
    )
    (net (code "42") (name "unconnected-(U$2-NC-PadP$2)") (class "Default")
      (node (ref "U$2") (pin "P$2") (pinfunction "NC_P$2") (pintype "no_connect"))
    )
    (net (code "43") (name "unconnected-(U$2-NC-PadP$11)") (class "Default")
      (node (ref "U$2") (pin "P$11") (pinfunction "NC_P$11") (pintype "no_connect"))
    )
    (net (code "44") (name "unconnected-(U$7-NC-PadP$1)") (class "Default")
      (node (ref "U$7") (pin "P$1") (pinfunction "NC_P$1") (pintype "no_connect"))
    )
    (net (code "45") (name "unconnected-(U$7-NC-PadP$2)") (class "Default")
      (node (ref "U$7") (pin "P$2") (pinfunction "NC_P$2") (pintype "no_connect"))
    )
    (net (code "46") (name "unconnected-(U$7-NC-PadP$6)") (class "Default")
      (node (ref "U$7") (pin "P$6") (pinfunction "NC_P$6") (pintype "no_connect"))
    )
    (net (code "47") (name "unconnected-(U$7-NC-PadP$9)") (class "Default")
      (node (ref "U$7") (pin "P$9") (pinfunction "NC_P$9") (pintype "no_connect"))
    )
    (net (code "48") (name "unconnected-(U$7-NC-PadP$12)") (class "Default")
      (node (ref "U$7") (pin "P$12") (pinfunction "NC_P$12") (pintype "no_connect"))
    )
    (net (code "49") (name "unconnected-(U$7-NC-PadP$13)") (class "Default")
      (node (ref "U$7") (pin "P$13") (pinfunction "NC_P$13") (pintype "bidirectional"))
    )
    (net (code "50") (name "unconnected-(U$7-NC-PadP$14)") (class "Default")
      (node (ref "U$7") (pin "P$14") (pinfunction "NC_P$14") (pintype "bidirectional"))
    )
  )
)
